# Connectors.net
KiCad netlist of a schematic drawn in Altium Designer
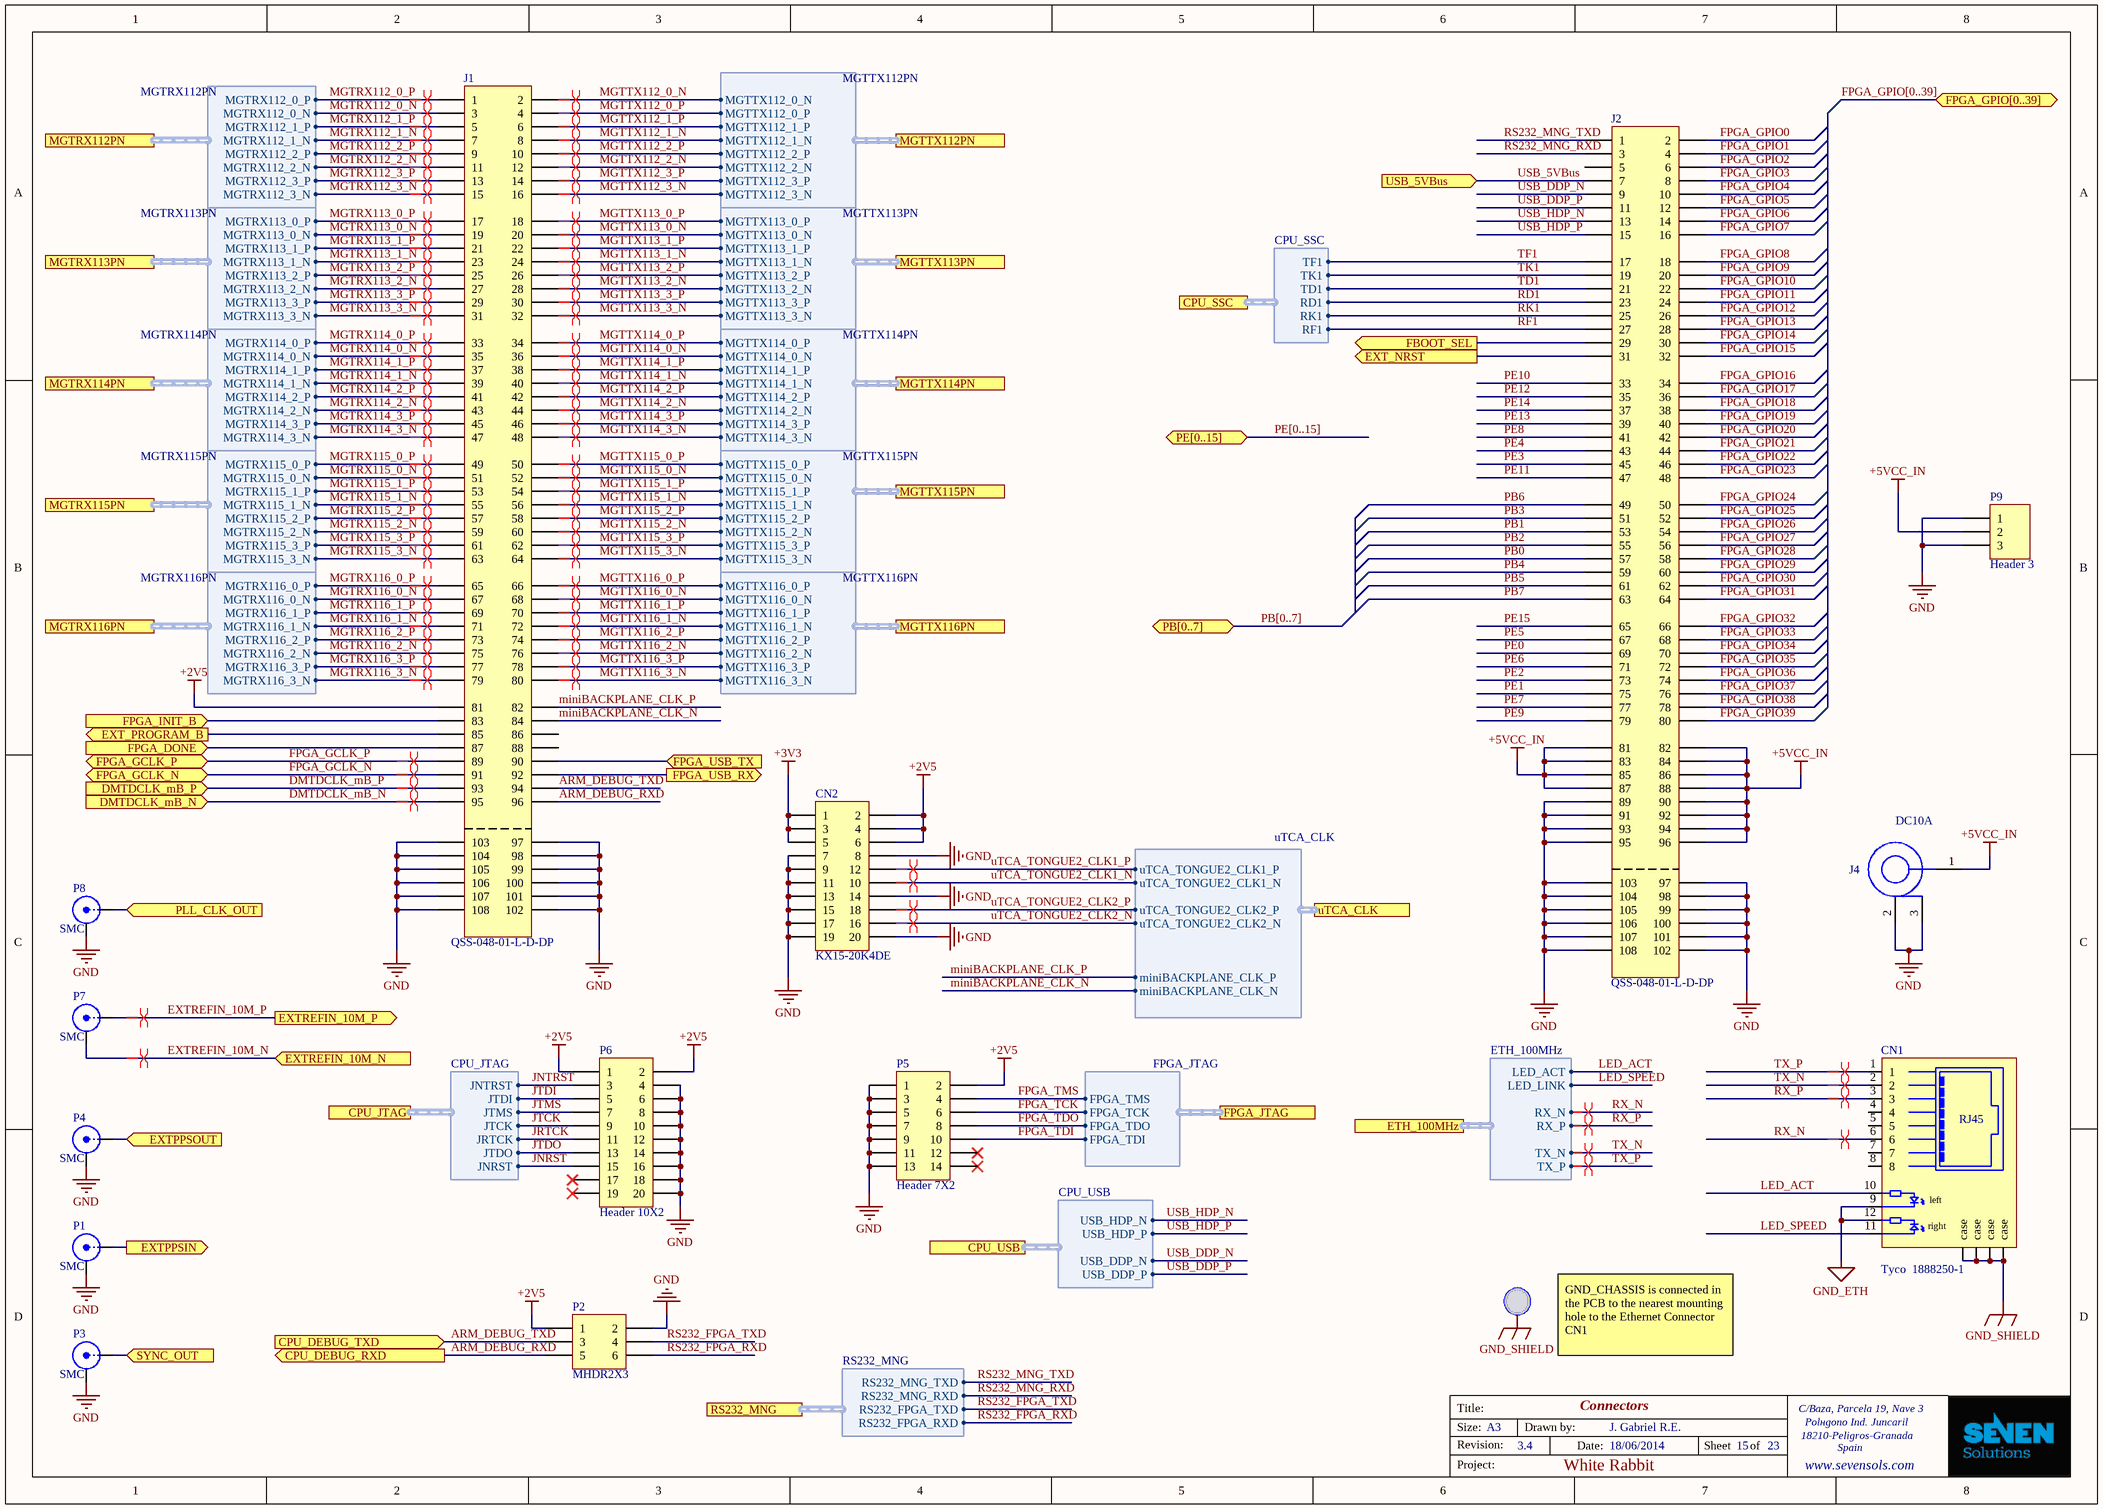
[diagram p0: Connectors.SchDoc]

(export (version "E")
  (design (tool "Eeschema 10.0.6"))
  (components
    (comp (ref "CN1")
      (value "Tyco  1888250-1")
      (footprint "TYCO_ETHERNET_1888250-1")
      (description "low profile uTCA Ethernet jack (RJ45)")
      (libsource (lib "wr_switch") (part "CON_ETHERNET_TYCO_1888250-1"))
    )
    (comp (ref "CN2")
      (value "KX15-20K4DE")
      (footprint "JAE_KX15_20P")
      (description "multipin B2B connector (plug)")
      (libsource (lib "wr_switch") (part "KX15_20p"))
    )
    (comp (ref "J1")
      (value "QSS-048-01-L-D-DP")
      (footprint "QSS-048-01-X-D-DP-A")
      (libsource (lib "wr_switch") (part "QSS-048-01-L-D-DP"))
    )
    (comp (ref "J2")
      (value "QSS-048-01-L-D-DP")
      (footprint "QSS-048-01-X-D-DP-A")
      (description "High Speed Ground Plane Header")
      (libsource (lib "wr_switch") (part "QSS-048-01-L-D-DP"))
    )
    (comp (ref "J4")
      (value "DC10A")
      (footprint "dc-10")
      (description "Power Jack 5A @ 12V")
      (libsource (lib "wr_switch") (part "PWR_JACK"))
    )
    (comp (ref "P1")
      (value "SMC")
      (footprint "SMB_V-RJ45")
      (description "SMB Straight Connector")
      (fields (field (name "PUBLISHER") "Altium Limited"))
      (libsource (lib "Miscellaneous Connectors") (part "SMB"))
    )
    (comp (ref "P2")
      (value "MHDR2X3")
      (footprint "7S_WR:HDR2x3_M22")
      (description "SMD Header, 3-Pin, Dual row, 2.54mm pitch")
      (libsource (lib "Miscellaneous Connectors") (part "MHDR2X3"))
    )
    (comp (ref "P3")
      (value "SMC")
      (footprint "SMB_V-RJ45")
      (description "SMB Straight Connector")
      (fields (field (name "PUBLISHER") "Altium Limited"))
      (libsource (lib "Miscellaneous Connectors") (part "SMB"))
    )
    (comp (ref "P4")
      (value "SMC")
      (footprint "SMB_V-RJ45")
      (description "SMB Straight Connector")
      (fields (field (name "PUBLISHER") "Altium Limited"))
      (libsource (lib "Miscellaneous Connectors") (part "SMB"))
    )
    (comp (ref "P5")
      (value "Header 7X2")
      (footprint "7S_WR:CONN_HDR_SMD_2mm_2x7")
      (description "Header, 7-Pin, Dual row, 2.0 mm pitch")
      (fields (field (name "PUBLISHER") "Altium Limited"))
      (libsource (lib "Miscellaneous Connectors") (part "Header 7X2"))
    )
    (comp (ref "P6")
      (value "Header 10X2")
      (footprint "7S_WR:HDR2X10_SBH11")
      (description "Header, 10-Pin, Dual row, 2.54mm pitch")
      (fields (field (name "MANUFACTURER") "Sullis Connectors") (field (name "PUBLISHER") "Altium Limited"))
      (libsource (lib "Miscellaneous Connectors") (part "Header 10X2"))
    )
    (comp (ref "P7")
      (value "SMC")
      (footprint "SMB_V-RJ45")
      (description "SMB Straight Connector")
      (fields (field (name "PUBLISHER") "Altium Limited"))
      (libsource (lib "Miscellaneous Connectors") (part "SMB"))
    )
    (comp (ref "P8")
      (value "SMC")
      (footprint "SMB_V-RJ45")
      (description "SMB Straight Connector")
      (fields (field (name "PUBLISHER") "Altium Limited"))
      (libsource (lib "Miscellaneous Connectors") (part "SMB"))
    )
    (comp (ref "P9")
      (value "Header 3")
      (footprint "7S_WR:HDR1x3_BG055")
      (description "Header, 3-Pin")
      (fields (field (name "PUBLISHER") "Altium Limited"))
      (libsource (lib "Miscellaneous Connectors") (part "Header 3"))
    )
  )
  (nets
    (net (code "18") (name "+2V5") (class "Default")
      (node (ref "CN2") (pin "2") (pinfunction "2_2") (pintype "passive"))
      (node (ref "CN2") (pin "4") (pinfunction "4_4") (pintype "passive"))
      (node (ref "CN2") (pin "6") (pinfunction "6_6") (pintype "passive"))
      (node (ref "J1") (pin "81") (pinfunction "81_81") (pintype "passive"))
      (node (ref "P2") (pin "1") (pinfunction "1_1") (pintype "passive"))
      (node (ref "P5") (pin "2") (pinfunction "2_2") (pintype "passive"))
      (node (ref "P6") (pin "1") (pinfunction "1_1") (pintype "passive"))
      (node (ref "P6") (pin "2") (pinfunction "2_2") (pintype "passive"))
    )
    (net (code "19") (name "+3V3") (class "Default")
      (node (ref "CN2") (pin "1") (pinfunction "1_1") (pintype "passive"))
      (node (ref "CN2") (pin "3") (pinfunction "3_3") (pintype "passive"))
      (node (ref "CN2") (pin "5") (pinfunction "5_5") (pintype "passive"))
    )
    (net (code "20") (name "+5VCC_IN") (class "Default")
      (node (ref "J2") (pin "81") (pinfunction "81_81") (pintype "passive"))
      (node (ref "J2") (pin "82") (pinfunction "82_82") (pintype "passive"))
      (node (ref "J2") (pin "83") (pinfunction "83_83") (pintype "passive"))
      (node (ref "J2") (pin "84") (pinfunction "84_84") (pintype "passive"))
      (node (ref "J2") (pin "85") (pinfunction "85_85") (pintype "passive"))
      (node (ref "J2") (pin "86") (pinfunction "86_86") (pintype "passive"))
      (node (ref "J2") (pin "87") (pinfunction "87_87") (pintype "passive"))
      (node (ref "J2") (pin "88") (pinfunction "88_88") (pintype "passive"))
      (node (ref "J2") (pin "90") (pinfunction "90_90") (pintype "passive"))
      (node (ref "J2") (pin "92") (pinfunction "92_92") (pintype "passive"))
      (node (ref "J2") (pin "94") (pinfunction "94_94") (pintype "passive"))
      (node (ref "J2") (pin "96") (pinfunction "96_96") (pintype "passive"))
      (node (ref "J4") (pin "1") (pinfunction "P1_1") (pintype "power_in"))
      (node (ref "P9") (pin "2") (pinfunction "2_2") (pintype "passive"))
    )
    (net (code "21") (name "/ARM_DEBUG_RXD") (class "Default")
      (node (ref "J1") (pin "96") (pinfunction "96_96") (pintype "passive"))
      (node (ref "P2") (pin "5") (pinfunction "5_5") (pintype "passive"))
    )
    (net (code "22") (name "/ARM_DEBUG_TXD") (class "Default")
      (node (ref "J1") (pin "94") (pinfunction "94_94") (pintype "passive"))
      (node (ref "P2") (pin "3") (pinfunction "3_3") (pintype "passive"))
    )
    (net (code "23") (name "/DMTDCLK_mB_N") (class "Default")
      (node (ref "J1") (pin "95") (pinfunction "95_95") (pintype "passive"))
    )
    (net (code "24") (name "/DMTDCLK_mB_P") (class "Default")
      (node (ref "J1") (pin "93") (pinfunction "93_93") (pintype "passive"))
    )
    (net (code "25") (name "/EXTPPSIN") (class "Default")
      (node (ref "P1") (pin "1") (pinfunction "X_1") (pintype "passive"))
    )
    (net (code "26") (name "/EXTPPSOUT") (class "Default")
      (node (ref "P4") (pin "1") (pinfunction "X_1") (pintype "passive"))
    )
    (net (code "27") (name "/EXTREFIN_10M_N") (class "Default")
      (node (ref "P7") (pin "2") (pinfunction "Y_2") (pintype "passive"))
    )
    (net (code "28") (name "/EXTREFIN_10M_P") (class "Default")
      (node (ref "P7") (pin "1") (pinfunction "X_1") (pintype "passive"))
    )
    (net (code "29") (name "/EXT_NRST") (class "Default")
      (node (ref "J2") (pin "31") (pinfunction "31_31") (pintype "passive"))
    )
    (net (code "30") (name "/EXT_PROGRAM_B") (class "Default")
      (node (ref "J1") (pin "85") (pinfunction "85_85") (pintype "passive"))
    )
    (net (code "31") (name "/FBOOT_SEL") (class "Default")
      (node (ref "J2") (pin "29") (pinfunction "29_29") (pintype "passive"))
    )
    (net (code "32") (name "/FPGA_DONE") (class "Default")
      (node (ref "J1") (pin "87") (pinfunction "87_87") (pintype "passive"))
    )
    (net (code "33") (name "/FPGA_GCLK_N") (class "Default")
      (node (ref "J1") (pin "91") (pinfunction "91_91") (pintype "passive"))
    )
    (net (code "34") (name "/FPGA_GCLK_P") (class "Default")
      (node (ref "J1") (pin "89") (pinfunction "89_89") (pintype "passive"))
    )
    (net (code "35") (name "/FPGA_GPIO0") (class "Default")
      (node (ref "J2") (pin "2") (pinfunction "2_2") (pintype "passive"))
    )
    (net (code "36") (name "/FPGA_GPIO1") (class "Default")
      (node (ref "J2") (pin "4") (pinfunction "4_4") (pintype "passive"))
    )
    (net (code "37") (name "/FPGA_GPIO2") (class "Default")
      (node (ref "J2") (pin "6") (pinfunction "6_6") (pintype "passive"))
    )
    (net (code "38") (name "/FPGA_GPIO3") (class "Default")
      (node (ref "J2") (pin "8") (pinfunction "8_8") (pintype "passive"))
    )
    (net (code "39") (name "/FPGA_GPIO4") (class "Default")
      (node (ref "J2") (pin "10") (pinfunction "10_10") (pintype "passive"))
    )
    (net (code "40") (name "/FPGA_GPIO5") (class "Default")
      (node (ref "J2") (pin "12") (pinfunction "12_12") (pintype "passive"))
    )
    (net (code "41") (name "/FPGA_GPIO6") (class "Default")
      (node (ref "J2") (pin "14") (pinfunction "14_14") (pintype "passive"))
    )
    (net (code "42") (name "/FPGA_GPIO7") (class "Default")
      (node (ref "J2") (pin "16") (pinfunction "16_16") (pintype "passive"))
    )
    (net (code "43") (name "/FPGA_GPIO8") (class "Default")
      (node (ref "J2") (pin "18") (pinfunction "18_18") (pintype "passive"))
    )
    (net (code "44") (name "/FPGA_GPIO9") (class "Default")
      (node (ref "J2") (pin "20") (pinfunction "20_20") (pintype "passive"))
    )
    (net (code "45") (name "/FPGA_GPIO10") (class "Default")
      (node (ref "J2") (pin "22") (pinfunction "22_22") (pintype "passive"))
    )
    (net (code "46") (name "/FPGA_GPIO11") (class "Default")
      (node (ref "J2") (pin "24") (pinfunction "24_24") (pintype "passive"))
    )
    (net (code "47") (name "/FPGA_GPIO12") (class "Default")
      (node (ref "J2") (pin "26") (pinfunction "26_26") (pintype "passive"))
    )
    (net (code "48") (name "/FPGA_GPIO13") (class "Default")
      (node (ref "J2") (pin "28") (pinfunction "28_28") (pintype "passive"))
    )
    (net (code "49") (name "/FPGA_GPIO14") (class "Default")
      (node (ref "J2") (pin "30") (pinfunction "30_30") (pintype "passive"))
    )
    (net (code "50") (name "/FPGA_GPIO15") (class "Default")
      (node (ref "J2") (pin "32") (pinfunction "32_32") (pintype "passive"))
    )
    (net (code "51") (name "/FPGA_GPIO16") (class "Default")
      (node (ref "J2") (pin "34") (pinfunction "34_34") (pintype "passive"))
    )
    (net (code "52") (name "/FPGA_GPIO17") (class "Default")
      (node (ref "J2") (pin "36") (pinfunction "36_36") (pintype "passive"))
    )
    (net (code "53") (name "/FPGA_GPIO18") (class "Default")
      (node (ref "J2") (pin "38") (pinfunction "38_38") (pintype "passive"))
    )
    (net (code "54") (name "/FPGA_GPIO19") (class "Default")
      (node (ref "J2") (pin "40") (pinfunction "40_40") (pintype "passive"))
    )
    (net (code "55") (name "/FPGA_GPIO20") (class "Default")
      (node (ref "J2") (pin "42") (pinfunction "42_42") (pintype "passive"))
    )
    (net (code "56") (name "/FPGA_GPIO21") (class "Default")
      (node (ref "J2") (pin "44") (pinfunction "44_44") (pintype "passive"))
    )
    (net (code "57") (name "/FPGA_GPIO22") (class "Default")
      (node (ref "J2") (pin "46") (pinfunction "46_46") (pintype "passive"))
    )
    (net (code "58") (name "/FPGA_GPIO23") (class "Default")
      (node (ref "J2") (pin "48") (pinfunction "48_48") (pintype "passive"))
    )
    (net (code "59") (name "/FPGA_GPIO24") (class "Default")
      (node (ref "J2") (pin "50") (pinfunction "50_50") (pintype "passive"))
    )
    (net (code "60") (name "/FPGA_GPIO25") (class "Default")
      (node (ref "J2") (pin "52") (pinfunction "52_52") (pintype "passive"))
    )
    (net (code "61") (name "/FPGA_GPIO26") (class "Default")
      (node (ref "J2") (pin "54") (pinfunction "54_54") (pintype "passive"))
    )
    (net (code "62") (name "/FPGA_GPIO27") (class "Default")
      (node (ref "J2") (pin "56") (pinfunction "56_56") (pintype "passive"))
    )
    (net (code "63") (name "/FPGA_GPIO28") (class "Default")
      (node (ref "J2") (pin "58") (pinfunction "58_58") (pintype "passive"))
    )
    (net (code "64") (name "/FPGA_GPIO29") (class "Default")
      (node (ref "J2") (pin "60") (pinfunction "60_60") (pintype "passive"))
    )
    (net (code "65") (name "/FPGA_GPIO30") (class "Default")
      (node (ref "J2") (pin "62") (pinfunction "62_62") (pintype "passive"))
    )
    (net (code "66") (name "/FPGA_GPIO31") (class "Default")
      (node (ref "J2") (pin "64") (pinfunction "64_64") (pintype "passive"))
    )
    (net (code "67") (name "/FPGA_GPIO32") (class "Default")
      (node (ref "J2") (pin "66") (pinfunction "66_66") (pintype "passive"))
    )
    (net (code "68") (name "/FPGA_GPIO33") (class "Default")
      (node (ref "J2") (pin "68") (pinfunction "68_68") (pintype "passive"))
    )
    (net (code "69") (name "/FPGA_GPIO34") (class "Default")
      (node (ref "J2") (pin "70") (pinfunction "70_70") (pintype "passive"))
    )
    (net (code "70") (name "/FPGA_GPIO35") (class "Default")
      (node (ref "J2") (pin "72") (pinfunction "72_72") (pintype "passive"))
    )
    (net (code "71") (name "/FPGA_GPIO36") (class "Default")
      (node (ref "J2") (pin "74") (pinfunction "74_74") (pintype "passive"))
    )
    (net (code "72") (name "/FPGA_GPIO37") (class "Default")
      (node (ref "J2") (pin "76") (pinfunction "76_76") (pintype "passive"))
    )
    (net (code "73") (name "/FPGA_GPIO38") (class "Default")
      (node (ref "J2") (pin "78") (pinfunction "78_78") (pintype "passive"))
    )
    (net (code "74") (name "/FPGA_GPIO39") (class "Default")
      (node (ref "J2") (pin "80") (pinfunction "80_80") (pintype "passive"))
    )
    (net (code "76") (name "/FPGA_INIT_B") (class "Default")
      (node (ref "J1") (pin "83") (pinfunction "83_83") (pintype "passive"))
    )
    (net (code "77") (name "/FPGA_TCK") (class "Default")
      (node (ref "P5") (pin "6") (pinfunction "6_6") (pintype "passive"))
    )
    (net (code "78") (name "/FPGA_TDI") (class "Default")
      (node (ref "P5") (pin "10") (pinfunction "10_10") (pintype "passive"))
    )
    (net (code "79") (name "/FPGA_TDO") (class "Default")
      (node (ref "P5") (pin "8") (pinfunction "8_8") (pintype "passive"))
    )
    (net (code "80") (name "/FPGA_TMS") (class "Default")
      (node (ref "P5") (pin "4") (pinfunction "4_4") (pintype "passive"))
    )
    (net (code "81") (name "/FPGA_USB_RX") (class "Default")
      (node (ref "J1") (pin "92") (pinfunction "92_92") (pintype "passive"))
    )
    (net (code "82") (name "/FPGA_USB_TX") (class "Default")
      (node (ref "J1") (pin "90") (pinfunction "90_90") (pintype "passive"))
    )
    (net (code "83") (name "/JNRST") (class "Default")
      (node (ref "P6") (pin "15") (pinfunction "15_15") (pintype "passive"))
    )
    (net (code "84") (name "/JNTRST") (class "Default")
      (node (ref "P6") (pin "3") (pinfunction "3_3") (pintype "passive"))
    )
    (net (code "85") (name "/JRTCK") (class "Default")
      (node (ref "P6") (pin "11") (pinfunction "11_11") (pintype "passive"))
    )
    (net (code "86") (name "/JTCK") (class "Default")
      (node (ref "P6") (pin "9") (pinfunction "9_9") (pintype "passive"))
    )
    (net (code "87") (name "/JTDI") (class "Default")
      (node (ref "P6") (pin "5") (pinfunction "5_5") (pintype "passive"))
    )
    (net (code "88") (name "/JTDO") (class "Default")
      (node (ref "P6") (pin "13") (pinfunction "13_13") (pintype "passive"))
    )
    (net (code "89") (name "/JTMS") (class "Default")
      (node (ref "P6") (pin "7") (pinfunction "7_7") (pintype "passive"))
    )
    (net (code "90") (name "/LED_ACT") (class "Default")
      (node (ref "CN1") (pin "10") (pinfunction "D1_10") (pintype "passive"))
    )
    (net (code "91") (name "/LED_SPEED") (class "Default")
      (node (ref "CN1") (pin "11") (pinfunction "D4_11") (pintype "passive"))
    )
    (net (code "92") (name "/MGTRX112_0_N") (class "Default")
      (node (ref "J1") (pin "3") (pinfunction "3_3") (pintype "passive"))
    )
    (net (code "93") (name "/MGTRX112_0_P") (class "Default")
      (node (ref "J1") (pin "1") (pinfunction "1_1") (pintype "passive"))
    )
    (net (code "94") (name "/MGTRX112_1_N") (class "Default")
      (node (ref "J1") (pin "7") (pinfunction "7_7") (pintype "passive"))
    )
    (net (code "95") (name "/MGTRX112_1_P") (class "Default")
      (node (ref "J1") (pin "5") (pinfunction "5_5") (pintype "passive"))
    )
    (net (code "96") (name "/MGTRX112_2_N") (class "Default")
      (node (ref "J1") (pin "11") (pinfunction "11_11") (pintype "passive"))
    )
    (net (code "97") (name "/MGTRX112_2_P") (class "Default")
      (node (ref "J1") (pin "9") (pinfunction "9_9") (pintype "passive"))
    )
    (net (code "98") (name "/MGTRX112_3_N") (class "Default")
      (node (ref "J1") (pin "15") (pinfunction "15_15") (pintype "passive"))
    )
    (net (code "99") (name "/MGTRX112_3_P") (class "Default")
      (node (ref "J1") (pin "13") (pinfunction "13_13") (pintype "passive"))
    )
    (net (code "100") (name "/MGTRX113_0_N") (class "Default")
      (node (ref "J1") (pin "19") (pinfunction "19_19") (pintype "passive"))
    )
    (net (code "101") (name "/MGTRX113_0_P") (class "Default")
      (node (ref "J1") (pin "17") (pinfunction "17_17") (pintype "passive"))
    )
    (net (code "102") (name "/MGTRX113_1_N") (class "Default")
      (node (ref "J1") (pin "23") (pinfunction "23_23") (pintype "passive"))
    )
    (net (code "103") (name "/MGTRX113_1_P") (class "Default")
      (node (ref "J1") (pin "21") (pinfunction "21_21") (pintype "passive"))
    )
    (net (code "104") (name "/MGTRX113_2_N") (class "Default")
      (node (ref "J1") (pin "27") (pinfunction "27_27") (pintype "passive"))
    )
    (net (code "105") (name "/MGTRX113_2_P") (class "Default")
      (node (ref "J1") (pin "25") (pinfunction "25_25") (pintype "passive"))
    )
    (net (code "106") (name "/MGTRX113_3_N") (class "Default")
      (node (ref "J1") (pin "31") (pinfunction "31_31") (pintype "passive"))
    )
    (net (code "107") (name "/MGTRX113_3_P") (class "Default")
      (node (ref "J1") (pin "29") (pinfunction "29_29") (pintype "passive"))
    )
    (net (code "108") (name "/MGTRX114_0_N") (class "Default")
      (node (ref "J1") (pin "35") (pinfunction "35_35") (pintype "passive"))
    )
    (net (code "109") (name "/MGTRX114_0_P") (class "Default")
      (node (ref "J1") (pin "33") (pinfunction "33_33") (pintype "passive"))
    )
    (net (code "110") (name "/MGTRX114_1_N") (class "Default")
      (node (ref "J1") (pin "39") (pinfunction "39_39") (pintype "passive"))
    )
    (net (code "111") (name "/MGTRX114_1_P") (class "Default")
      (node (ref "J1") (pin "37") (pinfunction "37_37") (pintype "passive"))
    )
    (net (code "112") (name "/MGTRX114_2_N") (class "Default")
      (node (ref "J1") (pin "43") (pinfunction "43_43") (pintype "passive"))
    )
    (net (code "113") (name "/MGTRX114_2_P") (class "Default")
      (node (ref "J1") (pin "41") (pinfunction "41_41") (pintype "passive"))
    )
    (net (code "114") (name "/MGTRX114_3_N") (class "Default")
      (node (ref "J1") (pin "47") (pinfunction "47_47") (pintype "passive"))
    )
    (net (code "115") (name "/MGTRX114_3_P") (class "Default")
      (node (ref "J1") (pin "45") (pinfunction "45_45") (pintype "passive"))
    )
    (net (code "116") (name "/MGTRX115_0_N") (class "Default")
      (node (ref "J1") (pin "51") (pinfunction "51_51") (pintype "passive"))
    )
    (net (code "117") (name "/MGTRX115_0_P") (class "Default")
      (node (ref "J1") (pin "49") (pinfunction "49_49") (pintype "passive"))
    )
    (net (code "118") (name "/MGTRX115_1_N") (class "Default")
      (node (ref "J1") (pin "55") (pinfunction "55_55") (pintype "passive"))
    )
    (net (code "119") (name "/MGTRX115_1_P") (class "Default")
      (node (ref "J1") (pin "53") (pinfunction "53_53") (pintype "passive"))
    )
    (net (code "120") (name "/MGTRX115_2_N") (class "Default")
      (node (ref "J1") (pin "59") (pinfunction "59_59") (pintype "passive"))
    )
    (net (code "121") (name "/MGTRX115_2_P") (class "Default")
      (node (ref "J1") (pin "57") (pinfunction "57_57") (pintype "passive"))
    )
    (net (code "122") (name "/MGTRX115_3_N") (class "Default")
      (node (ref "J1") (pin "63") (pinfunction "63_63") (pintype "passive"))
    )
    (net (code "123") (name "/MGTRX115_3_P") (class "Default")
      (node (ref "J1") (pin "61") (pinfunction "61_61") (pintype "passive"))
    )
    (net (code "124") (name "/MGTRX116_0_N") (class "Default")
      (node (ref "J1") (pin "67") (pinfunction "67_67") (pintype "passive"))
    )
    (net (code "125") (name "/MGTRX116_0_P") (class "Default")
      (node (ref "J1") (pin "65") (pinfunction "65_65") (pintype "passive"))
    )
    (net (code "126") (name "/MGTRX116_1_N") (class "Default")
      (node (ref "J1") (pin "71") (pinfunction "71_71") (pintype "passive"))
    )
    (net (code "127") (name "/MGTRX116_1_P") (class "Default")
      (node (ref "J1") (pin "69") (pinfunction "69_69") (pintype "passive"))
    )
    (net (code "128") (name "/MGTRX116_2_N") (class "Default")
      (node (ref "J1") (pin "75") (pinfunction "75_75") (pintype "passive"))
    )
    (net (code "129") (name "/MGTRX116_2_P") (class "Default")
      (node (ref "J1") (pin "73") (pinfunction "73_73") (pintype "passive"))
    )
    (net (code "130") (name "/MGTRX116_3_N") (class "Default")
      (node (ref "J1") (pin "79") (pinfunction "79_79") (pintype "passive"))
    )
    (net (code "131") (name "/MGTRX116_3_P") (class "Default")
      (node (ref "J1") (pin "77") (pinfunction "77_77") (pintype "passive"))
    )
    (net (code "132") (name "/MGTTX112_0_N") (class "Default")
      (node (ref "J1") (pin "2") (pinfunction "2_2") (pintype "passive"))
    )
    (net (code "133") (name "/MGTTX112_0_P") (class "Default")
      (node (ref "J1") (pin "4") (pinfunction "4_4") (pintype "passive"))
    )
    (net (code "134") (name "/MGTTX112_1_N") (class "Default")
      (node (ref "J1") (pin "8") (pinfunction "8_8") (pintype "passive"))
    )
    (net (code "135") (name "/MGTTX112_1_P") (class "Default")
      (node (ref "J1") (pin "6") (pinfunction "6_6") (pintype "passive"))
    )
    (net (code "136") (name "/MGTTX112_2_N") (class "Default")
      (node (ref "J1") (pin "12") (pinfunction "12_12") (pintype "passive"))
    )
    (net (code "137") (name "/MGTTX112_2_P") (class "Default")
      (node (ref "J1") (pin "10") (pinfunction "10_10") (pintype "passive"))
    )
    (net (code "138") (name "/MGTTX112_3_N") (class "Default")
      (node (ref "J1") (pin "16") (pinfunction "16_16") (pintype "passive"))
    )
    (net (code "139") (name "/MGTTX112_3_P") (class "Default")
      (node (ref "J1") (pin "14") (pinfunction "14_14") (pintype "passive"))
    )
    (net (code "140") (name "/MGTTX113_0_N") (class "Default")
      (node (ref "J1") (pin "20") (pinfunction "20_20") (pintype "passive"))
    )
    (net (code "141") (name "/MGTTX113_0_P") (class "Default")
      (node (ref "J1") (pin "18") (pinfunction "18_18") (pintype "passive"))
    )
    (net (code "142") (name "/MGTTX113_1_N") (class "Default")
      (node (ref "J1") (pin "24") (pinfunction "24_24") (pintype "passive"))
    )
    (net (code "143") (name "/MGTTX113_1_P") (class "Default")
      (node (ref "J1") (pin "22") (pinfunction "22_22") (pintype "passive"))
    )
    (net (code "144") (name "/MGTTX113_2_N") (class "Default")
      (node (ref "J1") (pin "28") (pinfunction "28_28") (pintype "passive"))
    )
    (net (code "145") (name "/MGTTX113_2_P") (class "Default")
      (node (ref "J1") (pin "26") (pinfunction "26_26") (pintype "passive"))
    )
    (net (code "146") (name "/MGTTX113_3_N") (class "Default")
      (node (ref "J1") (pin "32") (pinfunction "32_32") (pintype "passive"))
    )
    (net (code "147") (name "/MGTTX113_3_P") (class "Default")
      (node (ref "J1") (pin "30") (pinfunction "30_30") (pintype "passive"))
    )
    (net (code "148") (name "/MGTTX114_0_N") (class "Default")
      (node (ref "J1") (pin "36") (pinfunction "36_36") (pintype "passive"))
    )
    (net (code "149") (name "/MGTTX114_0_P") (class "Default")
      (node (ref "J1") (pin "34") (pinfunction "34_34") (pintype "passive"))
    )
    (net (code "150") (name "/MGTTX114_1_N") (class "Default")
      (node (ref "J1") (pin "40") (pinfunction "40_40") (pintype "passive"))
    )
    (net (code "151") (name "/MGTTX114_1_P") (class "Default")
      (node (ref "J1") (pin "38") (pinfunction "38_38") (pintype "passive"))
    )
    (net (code "152") (name "/MGTTX114_2_N") (class "Default")
      (node (ref "J1") (pin "44") (pinfunction "44_44") (pintype "passive"))
    )
    (net (code "153") (name "/MGTTX114_2_P") (class "Default")
      (node (ref "J1") (pin "42") (pinfunction "42_42") (pintype "passive"))
    )
    (net (code "154") (name "/MGTTX114_3_N") (class "Default")
      (node (ref "J1") (pin "48") (pinfunction "48_48") (pintype "passive"))
    )
    (net (code "155") (name "/MGTTX114_3_P") (class "Default")
      (node (ref "J1") (pin "46") (pinfunction "46_46") (pintype "passive"))
    )
    (net (code "156") (name "/MGTTX115_0_N") (class "Default")
      (node (ref "J1") (pin "52") (pinfunction "52_52") (pintype "passive"))
    )
    (net (code "157") (name "/MGTTX115_0_P") (class "Default")
      (node (ref "J1") (pin "50") (pinfunction "50_50") (pintype "passive"))
    )
    (net (code "158") (name "/MGTTX115_1_N") (class "Default")
      (node (ref "J1") (pin "56") (pinfunction "56_56") (pintype "passive"))
    )
    (net (code "159") (name "/MGTTX115_1_P") (class "Default")
      (node (ref "J1") (pin "54") (pinfunction "54_54") (pintype "passive"))
    )
    (net (code "160") (name "/MGTTX115_2_N") (class "Default")
      (node (ref "J1") (pin "60") (pinfunction "60_60") (pintype "passive"))
    )
    (net (code "161") (name "/MGTTX115_2_P") (class "Default")
      (node (ref "J1") (pin "58") (pinfunction "58_58") (pintype "passive"))
    )
    (net (code "162") (name "/MGTTX115_3_N") (class "Default")
      (node (ref "J1") (pin "64") (pinfunction "64_64") (pintype "passive"))
    )
    (net (code "163") (name "/MGTTX115_3_P") (class "Default")
      (node (ref "J1") (pin "62") (pinfunction "62_62") (pintype "passive"))
    )
    (net (code "164") (name "/MGTTX116_0_N") (class "Default")
      (node (ref "J1") (pin "68") (pinfunction "68_68") (pintype "passive"))
    )
    (net (code "165") (name "/MGTTX116_0_P") (class "Default")
      (node (ref "J1") (pin "66") (pinfunction "66_66") (pintype "passive"))
    )
    (net (code "166") (name "/MGTTX116_1_N") (class "Default")
      (node (ref "J1") (pin "72") (pinfunction "72_72") (pintype "passive"))
    )
    (net (code "167") (name "/MGTTX116_1_P") (class "Default")
      (node (ref "J1") (pin "70") (pinfunction "70_70") (pintype "passive"))
    )
    (net (code "168") (name "/MGTTX116_2_N") (class "Default")
      (node (ref "J1") (pin "76") (pinfunction "76_76") (pintype "passive"))
    )
    (net (code "169") (name "/MGTTX116_2_P") (class "Default")
      (node (ref "J1") (pin "74") (pinfunction "74_74") (pintype "passive"))
    )
    (net (code "170") (name "/MGTTX116_3_N") (class "Default")
      (node (ref "J1") (pin "80") (pinfunction "80_80") (pintype "passive"))
    )
    (net (code "171") (name "/MGTTX116_3_P") (class "Default")
      (node (ref "J1") (pin "78") (pinfunction "78_78") (pintype "passive"))
    )
    (net (code "172") (name "/PB0") (class "Default")
      (node (ref "J2") (pin "57") (pinfunction "57_57") (pintype "passive"))
    )
    (net (code "173") (name "/PB1") (class "Default")
      (node (ref "J2") (pin "53") (pinfunction "53_53") (pintype "passive"))
    )
    (net (code "174") (name "/PB2") (class "Default")
      (node (ref "J2") (pin "55") (pinfunction "55_55") (pintype "passive"))
    )
    (net (code "175") (name "/PB3") (class "Default")
      (node (ref "J2") (pin "51") (pinfunction "51_51") (pintype "passive"))
    )
    (net (code "176") (name "/PB4") (class "Default")
      (node (ref "J2") (pin "59") (pinfunction "59_59") (pintype "passive"))
    )
    (net (code "177") (name "/PB5") (class "Default")
      (node (ref "J2") (pin "61") (pinfunction "61_61") (pintype "passive"))
    )
    (net (code "178") (name "/PB6") (class "Default")
      (node (ref "J2") (pin "49") (pinfunction "49_49") (pintype "passive"))
    )
    (net (code "179") (name "/PB7") (class "Default")
      (node (ref "J2") (pin "63") (pinfunction "63_63") (pintype "passive"))
    )
    (net (code "181") (name "/PE0") (class "Default")
      (node (ref "J2") (pin "69") (pinfunction "69_69") (pintype "passive"))
    )
    (net (code "182") (name "/PE1") (class "Default")
      (node (ref "J2") (pin "75") (pinfunction "75_75") (pintype "passive"))
    )
    (net (code "183") (name "/PE2") (class "Default")
      (node (ref "J2") (pin "73") (pinfunction "73_73") (pintype "passive"))
    )
    (net (code "184") (name "/PE3") (class "Default")
      (node (ref "J2") (pin "45") (pinfunction "45_45") (pintype "passive"))
    )
    (net (code "185") (name "/PE4") (class "Default")
      (node (ref "J2") (pin "43") (pinfunction "43_43") (pintype "passive"))
    )
    (net (code "186") (name "/PE5") (class "Default")
      (node (ref "J2") (pin "67") (pinfunction "67_67") (pintype "passive"))
    )
    (net (code "187") (name "/PE6") (class "Default")
      (node (ref "J2") (pin "71") (pinfunction "71_71") (pintype "passive"))
    )
    (net (code "188") (name "/PE7") (class "Default")
      (node (ref "J2") (pin "77") (pinfunction "77_77") (pintype "passive"))
    )
    (net (code "189") (name "/PE8") (class "Default")
      (node (ref "J2") (pin "41") (pinfunction "41_41") (pintype "passive"))
    )
    (net (code "190") (name "/PE9") (class "Default")
      (node (ref "J2") (pin "79") (pinfunction "79_79") (pintype "passive"))
    )
    (net (code "191") (name "/PE10") (class "Default")
      (node (ref "J2") (pin "33") (pinfunction "33_33") (pintype "passive"))
    )
    (net (code "192") (name "/PE11") (class "Default")
      (node (ref "J2") (pin "47") (pinfunction "47_47") (pintype "passive"))
    )
    (net (code "193") (name "/PE12") (class "Default")
      (node (ref "J2") (pin "35") (pinfunction "35_35") (pintype "passive"))
    )
    (net (code "194") (name "/PE13") (class "Default")
      (node (ref "J2") (pin "39") (pinfunction "39_39") (pintype "passive"))
    )
    (net (code "195") (name "/PE14") (class "Default")
      (node (ref "J2") (pin "37") (pinfunction "37_37") (pintype "passive"))
    )
    (net (code "196") (name "/PE15") (class "Default")
      (node (ref "J2") (pin "65") (pinfunction "65_65") (pintype "passive"))
    )
    (net (code "198") (name "/PLL_CLK_OUT") (class "Default")
      (node (ref "P8") (pin "1") (pinfunction "X_1") (pintype "passive"))
    )
    (net (code "199") (name "/RD1") (class "Default")
      (node (ref "J2") (pin "23") (pinfunction "23_23") (pintype "passive"))
    )
    (net (code "200") (name "/RF1") (class "Default")
      (node (ref "J2") (pin "27") (pinfunction "27_27") (pintype "passive"))
    )
    (net (code "201") (name "/RK1") (class "Default")
      (node (ref "J2") (pin "25") (pinfunction "25_25") (pintype "passive"))
    )
    (net (code "202") (name "/RS232_FPGA_RXD") (class "Default")
      (node (ref "P2") (pin "6") (pinfunction "6_6") (pintype "passive"))
    )
    (net (code "203") (name "/RS232_FPGA_TXD") (class "Default")
      (node (ref "P2") (pin "4") (pinfunction "4_4") (pintype "passive"))
    )
    (net (code "204") (name "/RS232_MNG_RXD") (class "Default")
      (node (ref "J2") (pin "3") (pinfunction "3_3") (pintype "passive"))
    )
    (net (code "205") (name "/RS232_MNG_TXD") (class "Default")
      (node (ref "J2") (pin "1") (pinfunction "1_1") (pintype "passive"))
    )
    (net (code "206") (name "/RX_N") (class "Default")
      (node (ref "CN1") (pin "6") (pinfunction "6_6") (pintype "passive"))
    )
    (net (code "207") (name "/RX_P") (class "Default")
      (node (ref "CN1") (pin "3") (pinfunction "3_3") (pintype "passive"))
    )
    (net (code "208") (name "/SYNC_OUT") (class "Default")
      (node (ref "P3") (pin "1") (pinfunction "X_1") (pintype "passive"))
    )
    (net (code "209") (name "/TD1") (class "Default")
      (node (ref "J2") (pin "21") (pinfunction "21_21") (pintype "passive"))
    )
    (net (code "210") (name "/TF1") (class "Default")
      (node (ref "J2") (pin "17") (pinfunction "17_17") (pintype "passive"))
    )
    (net (code "211") (name "/TK1") (class "Default")
      (node (ref "J2") (pin "19") (pinfunction "19_19") (pintype "passive"))
    )
    (net (code "212") (name "/TX_N") (class "Default")
      (node (ref "CN1") (pin "2") (pinfunction "2_2") (pintype "passive"))
    )
    (net (code "213") (name "/TX_P") (class "Default")
      (node (ref "CN1") (pin "1") (pinfunction "1_1") (pintype "passive"))
    )
    (net (code "214") (name "/USB_5VBus") (class "Default")
      (node (ref "J2") (pin "7") (pinfunction "7_7") (pintype "passive"))
    )
    (net (code "215") (name "/USB_DDP_N") (class "Default")
      (node (ref "J2") (pin "9") (pinfunction "9_9") (pintype "passive"))
    )
    (net (code "216") (name "/USB_DDP_P") (class "Default")
      (node (ref "J2") (pin "11") (pinfunction "11_11") (pintype "passive"))
    )
    (net (code "217") (name "/USB_HDP_N") (class "Default")
      (node (ref "J2") (pin "13") (pinfunction "13_13") (pintype "passive"))
    )
    (net (code "218") (name "/USB_HDP_P") (class "Default")
      (node (ref "J2") (pin "15") (pinfunction "15_15") (pintype "passive"))
    )
    (net (code "219") (name "/miniBACKPLANE_CLK_N") (class "Default")
      (node (ref "J1") (pin "84") (pinfunction "84_84") (pintype "passive"))
    )
    (net (code "220") (name "/miniBACKPLANE_CLK_P") (class "Default")
      (node (ref "J1") (pin "82") (pinfunction "82_82") (pintype "passive"))
    )
    (net (code "221") (name "/uTCA_TONGUE2_CLK1_N") (class "Default")
      (node (ref "CN2") (pin "10") (pinfunction "10_10") (pintype "passive"))
    )
    (net (code "222") (name "/uTCA_TONGUE2_CLK1_P") (class "Default")
      (node (ref "CN2") (pin "12") (pinfunction "12_12") (pintype "passive"))
    )
    (net (code "223") (name "/uTCA_TONGUE2_CLK2_N") (class "Default")
      (node (ref "CN2") (pin "16") (pinfunction "16_16") (pintype "passive"))
    )
    (net (code "224") (name "/uTCA_TONGUE2_CLK2_P") (class "Default")
      (node (ref "CN2") (pin "18") (pinfunction "18_18") (pintype "passive"))
    )
    (net (code "242") (name "GND") (class "Default")
      (node (ref "CN2") (pin "11") (pinfunction "11_11") (pintype "passive"))
      (node (ref "CN2") (pin "13") (pinfunction "13_13") (pintype "passive"))
      (node (ref "CN2") (pin "14") (pinfunction "14_14") (pintype "passive"))
      (node (ref "CN2") (pin "15") (pinfunction "15_15") (pintype "passive"))
      (node (ref "CN2") (pin "17") (pinfunction "17_17") (pintype "passive"))
      (node (ref "CN2") (pin "19") (pinfunction "19_19") (pintype "passive"))
      (node (ref "CN2") (pin "20") (pinfunction "20_20") (pintype "passive"))
      (node (ref "CN2") (pin "7") (pinfunction "7_7") (pintype "passive"))
      (node (ref "CN2") (pin "8") (pinfunction "8_8") (pintype "passive"))
      (node (ref "CN2") (pin "9") (pinfunction "9_9") (pintype "passive"))
      (node (ref "J1") (pin "100") (pinfunction "100_100") (pintype "passive"))
      (node (ref "J1") (pin "101") (pinfunction "101_101") (pintype "passive"))
      (node (ref "J1") (pin "102") (pinfunction "102_102") (pintype "passive"))
      (node (ref "J1") (pin "103") (pinfunction "103_103") (pintype "passive"))
      (node (ref "J1") (pin "104") (pinfunction "104_104") (pintype "passive"))
      (node (ref "J1") (pin "105") (pinfunction "105_105") (pintype "passive"))
      (node (ref "J1") (pin "106") (pinfunction "106_106") (pintype "passive"))
      (node (ref "J1") (pin "107") (pinfunction "107_107") (pintype "passive"))
      (node (ref "J1") (pin "108") (pinfunction "108_108") (pintype "passive"))
      (node (ref "J1") (pin "97") (pinfunction "97_97") (pintype "passive"))
      (node (ref "J1") (pin "98") (pinfunction "98_98") (pintype "passive"))
      (node (ref "J1") (pin "99") (pinfunction "99_99") (pintype "passive"))
      (node (ref "J2") (pin "100") (pinfunction "100_100") (pintype "passive"))
      (node (ref "J2") (pin "101") (pinfunction "101_101") (pintype "passive"))
      (node (ref "J2") (pin "102") (pinfunction "102_102") (pintype "passive"))
      (node (ref "J2") (pin "103") (pinfunction "103_103") (pintype "passive"))
      (node (ref "J2") (pin "104") (pinfunction "104_104") (pintype "passive"))
      (node (ref "J2") (pin "105") (pinfunction "105_105") (pintype "passive"))
      (node (ref "J2") (pin "106") (pinfunction "106_106") (pintype "passive"))
      (node (ref "J2") (pin "107") (pinfunction "107_107") (pintype "passive"))
      (node (ref "J2") (pin "108") (pinfunction "108_108") (pintype "passive"))
      (node (ref "J2") (pin "89") (pinfunction "89_89") (pintype "passive"))
      (node (ref "J2") (pin "91") (pinfunction "91_91") (pintype "passive"))
      (node (ref "J2") (pin "93") (pinfunction "93_93") (pintype "passive"))
      (node (ref "J2") (pin "95") (pinfunction "95_95") (pintype "passive"))
      (node (ref "J2") (pin "97") (pinfunction "97_97") (pintype "passive"))
      (node (ref "J2") (pin "98") (pinfunction "98_98") (pintype "passive"))
      (node (ref "J2") (pin "99") (pinfunction "99_99") (pintype "passive"))
      (node (ref "J4") (pin "2") (pinfunction "P2_2") (pintype "power_in"))
      (node (ref "J4") (pin "3") (pinfunction "P3_3") (pintype "power_in"))
      (node (ref "P1") (pin "2") (pinfunction "Y_2") (pintype "passive"))
      (node (ref "P2") (pin "2") (pinfunction "2_2") (pintype "passive"))
      (node (ref "P3") (pin "2") (pinfunction "Y_2") (pintype "passive"))
      (node (ref "P4") (pin "2") (pinfunction "Y_2") (pintype "passive"))
      (node (ref "P5") (pin "1") (pinfunction "1_1") (pintype "passive"))
      (node (ref "P5") (pin "11") (pinfunction "11_11") (pintype "passive"))
      (node (ref "P5") (pin "13") (pinfunction "13_13") (pintype "passive"))
      (node (ref "P5") (pin "3") (pinfunction "3_3") (pintype "passive"))
      (node (ref "P5") (pin "5") (pinfunction "5_5") (pintype "passive"))
      (node (ref "P5") (pin "7") (pinfunction "7_7") (pintype "passive"))
      (node (ref "P5") (pin "9") (pinfunction "9_9") (pintype "passive"))
      (node (ref "P6") (pin "10") (pinfunction "10_10") (pintype "passive"))
      (node (ref "P6") (pin "12") (pinfunction "12_12") (pintype "passive"))
      (node (ref "P6") (pin "14") (pinfunction "14_14") (pintype "passive"))
      (node (ref "P6") (pin "16") (pinfunction "16_16") (pintype "passive"))
      (node (ref "P6") (pin "18") (pinfunction "18_18") (pintype "passive"))
      (node (ref "P6") (pin "20") (pinfunction "20_20") (pintype "passive"))
      (node (ref "P6") (pin "4") (pinfunction "4_4") (pintype "passive"))
      (node (ref "P6") (pin "6") (pinfunction "6_6") (pintype "passive"))
      (node (ref "P6") (pin "8") (pinfunction "8_8") (pintype "passive"))
      (node (ref "P8") (pin "2") (pinfunction "Y_2") (pintype "passive"))
      (node (ref "P9") (pin "1") (pinfunction "1_1") (pintype "passive"))
      (node (ref "P9") (pin "3") (pinfunction "3_3") (pintype "passive"))
    )
    (net (code "243") (name "GND_ETH") (class "Default")
      (node (ref "CN1") (pin "12") (pinfunction "D3_12") (pintype "passive"))
      (node (ref "CN1") (pin "9") (pinfunction "D2_9") (pintype "passive"))
    )
    (net (code "244") (name "GND_SHIELD") (class "Default")
      (node (ref "CN1") (pin "0") (pinfunction "case_0") (pintype "passive"))
    )
    (net (code "245") (name "unconnected-(CN1-Pad4)") (class "Default")
      (node (ref "CN1") (pin "4") (pinfunction "4_4") (pintype "passive"))
    )
    (net (code "246") (name "unconnected-(CN1-Pad5)") (class "Default")
      (node (ref "CN1") (pin "5") (pinfunction "5_5") (pintype "passive"))
    )
    (net (code "247") (name "unconnected-(CN1-Pad7)") (class "Default")
      (node (ref "CN1") (pin "7") (pinfunction "7_7") (pintype "passive"))
    )
    (net (code "248") (name "unconnected-(CN1-Pad8)") (class "Default")
      (node (ref "CN1") (pin "8") (pinfunction "8_8") (pintype "passive"))
    )
    (net (code "249") (name "unconnected-(J1-Pad86)") (class "Default")
      (node (ref "J1") (pin "86") (pinfunction "86_86") (pintype "passive"))
    )
    (net (code "250") (name "unconnected-(J1-Pad88)") (class "Default")
      (node (ref "J1") (pin "88") (pinfunction "88_88") (pintype "passive"))
    )
    (net (code "251") (name "unconnected-(J2-Pad5)") (class "Default")
      (node (ref "J2") (pin "5") (pinfunction "5_5") (pintype "passive"))
    )
    (net (code "252") (name "unconnected-(P5-Pad12)") (class "Default")
      (node (ref "P5") (pin "12") (pinfunction "12_12") (pintype "passive+no_connect"))
    )
    (net (code "253") (name "unconnected-(P5-Pad14)") (class "Default")
      (node (ref "P5") (pin "14") (pinfunction "14_14") (pintype "passive+no_connect"))
    )
    (net (code "254") (name "unconnected-(P6-Pad17)") (class "Default")
      (node (ref "P6") (pin "17") (pinfunction "17_17") (pintype "passive+no_connect"))
    )
    (net (code "255") (name "unconnected-(P6-Pad19)") (class "Default")
      (node (ref "P6") (pin "19") (pinfunction "19_19") (pintype "passive+no_connect"))
    )
  )
)
